# Pg2_B_Terminals_Balancing.net
KiCad netlist of a schematic drawn in Altium Designer
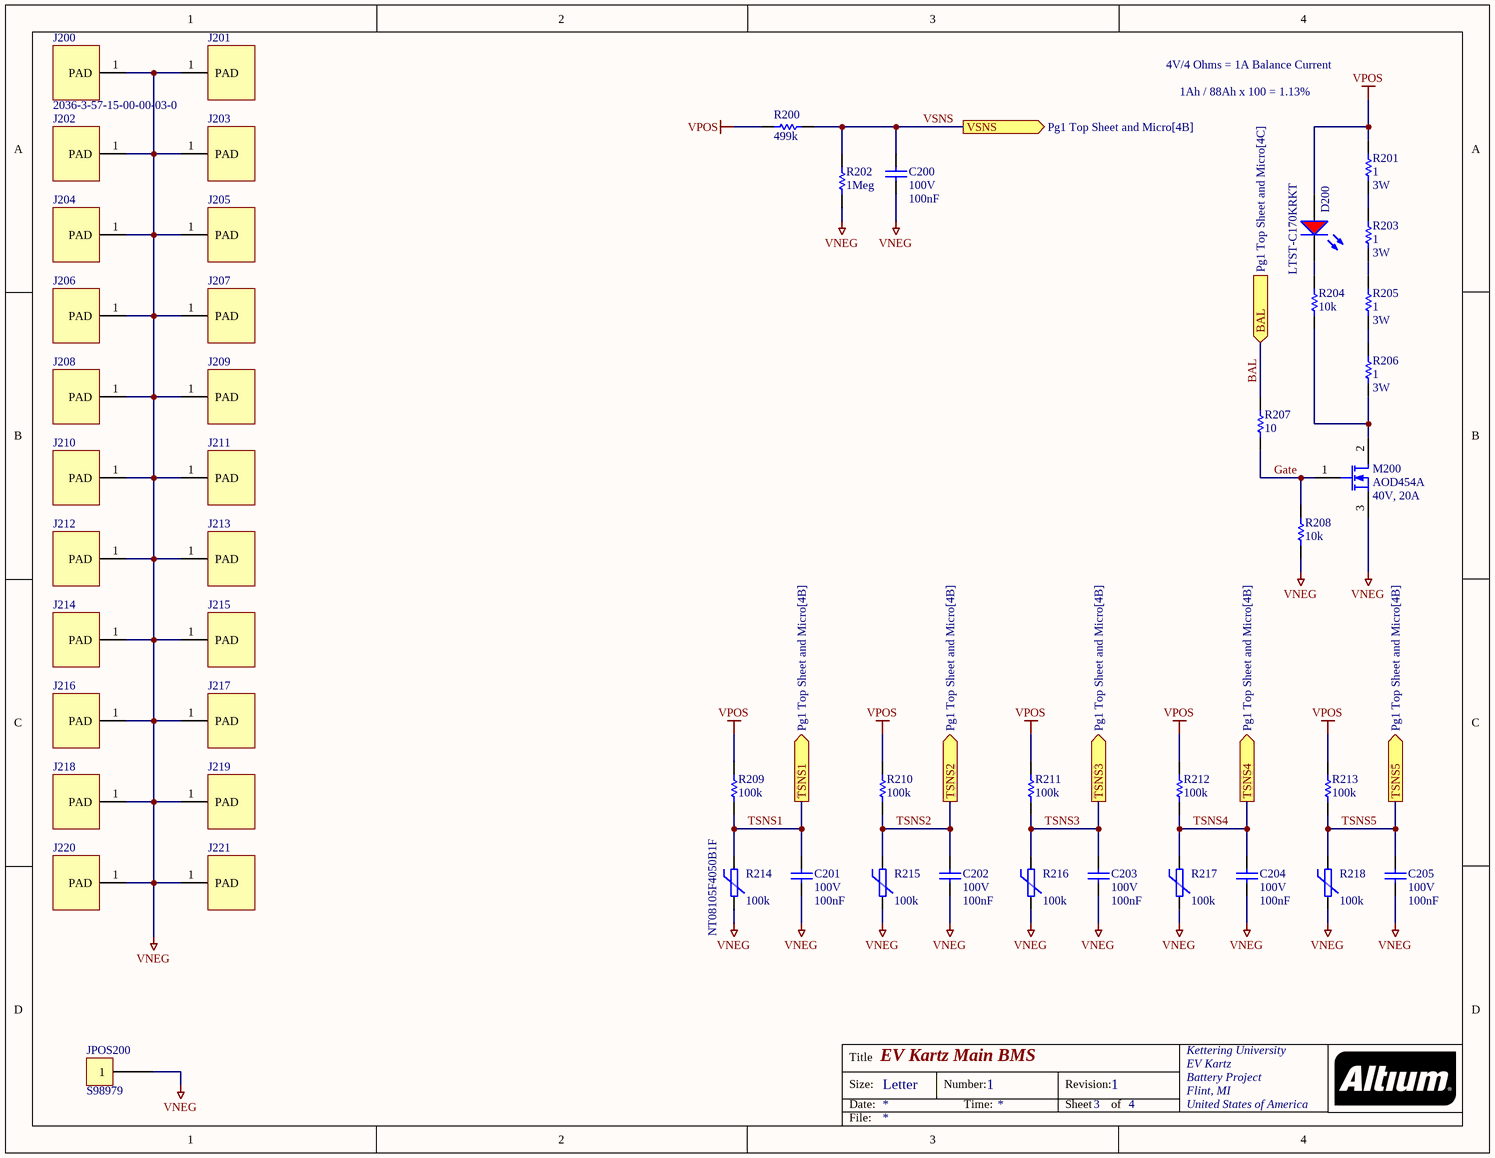
[diagram p0: Pg2 B Terminals & Balancing.SchDoc]

(export (version "E")
  (design (tool "Eeschema 10.0.6"))
  (components
    (comp (ref "C200")
      (value "100nF")
      (footprint "CAPC2012N")
      (description "Capacitor, Ceramic, 100nF, 100V, 0805, 10%, 125C")
      (fields (field (name "RATED") "100V") (field (name "Comment") "C0805C104K1RACAUTO"))
      (libsource (lib "SchLib - EE391 Master") (part "C0805C104K1RACAUTO"))
    )
    (comp (ref "C201")
      (value "100nF")
      (footprint "CAPC2012N")
      (description "Capacitor, Ceramic, 100nF, 100V, 0805, 10%, 125C")
      (fields (field (name "RATED") "100V") (field (name "Comment") "C0805C104K1RACAUTO"))
      (libsource (lib "SchLib - EE391 Master") (part "C0805C104K1RACAUTO"))
    )
    (comp (ref "C202")
      (value "100nF")
      (footprint "CAPC2012N")
      (description "Capacitor, Ceramic, 100nF, 100V, 0805, 10%, 125C")
      (fields (field (name "RATED") "100V") (field (name "Comment") "C0805C104K1RACAUTO"))
      (libsource (lib "SchLib - EE391 Master") (part "C0805C104K1RACAUTO"))
    )
    (comp (ref "C203")
      (value "100nF")
      (footprint "CAPC2012N")
      (description "Capacitor, Ceramic, 100nF, 100V, 0805, 10%, 125C")
      (fields (field (name "RATED") "100V") (field (name "Comment") "C0805C104K1RACAUTO"))
      (libsource (lib "SchLib - EE391 Master") (part "C0805C104K1RACAUTO"))
    )
    (comp (ref "C204")
      (value "100nF")
      (footprint "CAPC2012N")
      (description "Capacitor, Ceramic, 100nF, 100V, 0805, 10%, 125C")
      (fields (field (name "RATED") "100V") (field (name "Comment") "C0805C104K1RACAUTO"))
      (libsource (lib "SchLib - EE391 Master") (part "C0805C104K1RACAUTO"))
    )
    (comp (ref "C205")
      (value "100nF")
      (footprint "CAPC2012N")
      (description "Capacitor, Ceramic, 100nF, 100V, 0805, 10%, 125C")
      (fields (field (name "RATED") "100V") (field (name "Comment") "C0805C104K1RACAUTO"))
      (libsource (lib "SchLib - EE391 Master") (part "C0805C104K1RACAUTO"))
    )
    (comp (ref "D200")
      (value "LTST-C170KRKT")
      (footprint "DIO2012N-R")
      (description "LED, SMT 0805, Red, 2.0V, 20mA")
      (libsource (lib "SchLib - EE391 Master") (part "LTST-C170KRKT"))
    )
    (comp (ref "J200")
      (value "2036-3-57-15-00-00-03-0")
      (footprint "6mm Pad")
      (description "Hardware, Sprint Contact Surface")
      (libsource (lib "") (part "2036-3-57-15-00-00-03-0_1"))
    )
    (comp (ref "J201")
      (value "2036-3-57-15-00-00-03-0")
      (footprint "6mm Pad")
      (description "Hardware, Sprint Contact Surface")
      (libsource (lib "SchLib - EE391 Master") (part "2036-3-57-15-00-00-03-0"))
    )
    (comp (ref "J202")
      (value "2036-3-57-15-00-00-03-0")
      (footprint "6mm Pad")
      (description "Hardware, Sprint Contact Surface")
      (libsource (lib "") (part "2036-3-57-15-00-00-03-0_1"))
    )
    (comp (ref "J203")
      (value "2036-3-57-15-00-00-03-0")
      (footprint "6mm Pad")
      (description "Hardware, Sprint Contact Surface")
      (libsource (lib "SchLib - EE391 Master") (part "2036-3-57-15-00-00-03-0"))
    )
    (comp (ref "J204")
      (value "2036-3-57-15-00-00-03-0")
      (footprint "6mm Pad")
      (description "Hardware, Sprint Contact Surface")
      (libsource (lib "") (part "2036-3-57-15-00-00-03-0_1"))
    )
    (comp (ref "J205")
      (value "2036-3-57-15-00-00-03-0")
      (footprint "6mm Pad")
      (description "Hardware, Sprint Contact Surface")
      (libsource (lib "SchLib - EE391 Master") (part "2036-3-57-15-00-00-03-0"))
    )
    (comp (ref "J206")
      (value "2036-3-57-15-00-00-03-0")
      (footprint "6mm Pad")
      (description "Hardware, Sprint Contact Surface")
      (libsource (lib "") (part "2036-3-57-15-00-00-03-0_1"))
    )
    (comp (ref "J207")
      (value "2036-3-57-15-00-00-03-0")
      (footprint "6mm Pad")
      (description "Hardware, Sprint Contact Surface")
      (libsource (lib "SchLib - EE391 Master") (part "2036-3-57-15-00-00-03-0"))
    )
    (comp (ref "J208")
      (value "2036-3-57-15-00-00-03-0")
      (footprint "6mm Pad")
      (description "Hardware, Sprint Contact Surface")
      (libsource (lib "") (part "2036-3-57-15-00-00-03-0_1"))
    )
    (comp (ref "J209")
      (value "2036-3-57-15-00-00-03-0")
      (footprint "6mm Pad")
      (description "Hardware, Sprint Contact Surface")
      (libsource (lib "SchLib - EE391 Master") (part "2036-3-57-15-00-00-03-0"))
    )
    (comp (ref "J210")
      (value "2036-3-57-15-00-00-03-0")
      (footprint "6mm Pad")
      (description "Hardware, Sprint Contact Surface")
      (libsource (lib "") (part "2036-3-57-15-00-00-03-0_1"))
    )
    (comp (ref "J211")
      (value "2036-3-57-15-00-00-03-0")
      (footprint "6mm Pad")
      (description "Hardware, Sprint Contact Surface")
      (libsource (lib "SchLib - EE391 Master") (part "2036-3-57-15-00-00-03-0"))
    )
    (comp (ref "J212")
      (value "2036-3-57-15-00-00-03-0")
      (footprint "6mm Pad")
      (description "Hardware, Sprint Contact Surface")
      (libsource (lib "") (part "2036-3-57-15-00-00-03-0_1"))
    )
    (comp (ref "J213")
      (value "2036-3-57-15-00-00-03-0")
      (footprint "6mm Pad")
      (description "Hardware, Sprint Contact Surface")
      (libsource (lib "SchLib - EE391 Master") (part "2036-3-57-15-00-00-03-0"))
    )
    (comp (ref "J214")
      (value "2036-3-57-15-00-00-03-0")
      (footprint "6mm Pad")
      (description "Hardware, Sprint Contact Surface")
      (libsource (lib "") (part "2036-3-57-15-00-00-03-0_1"))
    )
    (comp (ref "J215")
      (value "2036-3-57-15-00-00-03-0")
      (footprint "6mm Pad")
      (description "Hardware, Sprint Contact Surface")
      (libsource (lib "SchLib - EE391 Master") (part "2036-3-57-15-00-00-03-0"))
    )
    (comp (ref "J216")
      (value "2036-3-57-15-00-00-03-0")
      (footprint "6mm Pad")
      (description "Hardware, Sprint Contact Surface")
      (libsource (lib "") (part "2036-3-57-15-00-00-03-0_1"))
    )
    (comp (ref "J217")
      (value "2036-3-57-15-00-00-03-0")
      (footprint "6mm Pad")
      (description "Hardware, Sprint Contact Surface")
      (libsource (lib "SchLib - EE391 Master") (part "2036-3-57-15-00-00-03-0"))
    )
    (comp (ref "J218")
      (value "2036-3-57-15-00-00-03-0")
      (footprint "6mm Pad")
      (description "Hardware, Sprint Contact Surface")
      (libsource (lib "") (part "2036-3-57-15-00-00-03-0_1"))
    )
    (comp (ref "J219")
      (value "2036-3-57-15-00-00-03-0")
      (footprint "6mm Pad")
      (description "Hardware, Sprint Contact Surface")
      (libsource (lib "SchLib - EE391 Master") (part "2036-3-57-15-00-00-03-0"))
    )
    (comp (ref "J220")
      (value "2036-3-57-15-00-00-03-0")
      (footprint "6mm Pad")
      (description "Hardware, Sprint Contact Surface")
      (libsource (lib "") (part "2036-3-57-15-00-00-03-0_1"))
    )
    (comp (ref "J221")
      (value "2036-3-57-15-00-00-03-0")
      (footprint "6mm Pad")
      (description "Hardware, Sprint Contact Surface")
      (libsource (lib "SchLib - EE391 Master") (part "2036-3-57-15-00-00-03-0"))
    )
    (comp (ref "JPOS200")
      (value "S98979")
      (footprint "S98979")
      (description "Screw Terminal M8, 360A")
      (libsource (lib "Connectors") (part "S98979"))
    )
    (comp (ref "M200")
      (value "AOD454A")
      (footprint "TO252-3N")
      (description "MOSFET, N-Ch, 40V, 20A, 430mOhm, TO252")
      (fields (field (name "RATED") "40V, 20A"))
      (libsource (lib "SchLib - EE391 Master") (part "AOD454A"))
    )
    (comp (ref "R200")
      (value "499k")
      (footprint "RESC2012N")
      (description "Resistor, Fixed, 499 kOhm, 0805, 1%, 1/8W")
      (fields (field (name "Comment") "ERJ-6ENF4993V"))
      (libsource (lib "SchLib - EE391 Master") (part "ERJ-6ENF4993V"))
    )
    (comp (ref "R201")
      (value "1")
      (footprint "RESC6432N")
      (description "Resistor, Power, 1 Ohm, 6432, 5%, 3W")
      (fields (field (name "RATED") "3W") (field (name "Comment") "35221R0JT"))
      (libsource (lib "SchLib - EE391 Master") (part "35221R0JT"))
    )
    (comp (ref "R202")
      (value "1Meg")
      (footprint "RESC2012N")
      (description "Resistor, Fixed, 1 MOhm, 0805, 1%, 1/8W")
      (fields (field (name "Comment") "ERJ-6ENF1004V"))
      (libsource (lib "SchLib - EE391 Master") (part "ERJ-6ENF1004V"))
    )
    (comp (ref "R203")
      (value "1")
      (footprint "RESC6432N")
      (description "Resistor, Power, 1 Ohm, 6432, 5%, 3W")
      (fields (field (name "RATED") "3W") (field (name "Comment") "35221R0JT"))
      (libsource (lib "SchLib - EE391 Master") (part "35221R0JT"))
    )
    (comp (ref "R204")
      (value "10k")
      (footprint "RESC2012N")
      (description "Resistor, Fixed, 10 kOhm, 0805, 1%, 1/8W")
      (fields (field (name "Comment") "ERJ-6ENF1002V"))
      (libsource (lib "SchLib - EE391 Master") (part "ERJ-6ENF1002V"))
    )
    (comp (ref "R205")
      (value "1")
      (footprint "RESC6432N")
      (description "Resistor, Power, 1 Ohm, 6432, 5%, 3W")
      (fields (field (name "RATED") "3W") (field (name "Comment") "35221R0JT"))
      (libsource (lib "SchLib - EE391 Master") (part "35221R0JT"))
    )
    (comp (ref "R206")
      (value "1")
      (footprint "RESC6432N")
      (description "Resistor, Power, 1 Ohm, 6432, 5%, 3W")
      (fields (field (name "RATED") "3W") (field (name "Comment") "35221R0JT"))
      (libsource (lib "SchLib - EE391 Master") (part "35221R0JT"))
    )
    (comp (ref "R207")
      (value "10")
      (footprint "RESC2012N")
      (description "Resistor, Fixed, 10 Ohm, 0805, 1%, 1/8W")
      (fields (field (name "Comment") "ERJ-6ENF10R0V"))
      (libsource (lib "SchLib - EE391 Master") (part "ERJ-6ENF10R0V"))
    )
    (comp (ref "R208")
      (value "10k")
      (footprint "RESC2012N")
      (description "Resistor, Fixed, 10 kOhm, 0805, 1%, 1/8W")
      (fields (field (name "Comment") "ERJ-6ENF1002V"))
      (libsource (lib "SchLib - EE391 Master") (part "ERJ-6ENF1002V"))
    )
    (comp (ref "R209")
      (value "100k")
      (footprint "RESC2012N")
      (description "Resistor, Fixed, 100 kOhm, 0805, 1%, 1/8W")
      (fields (field (name "Comment") "ERJ-6ENF1003V"))
      (libsource (lib "SchLib - EE391 Master") (part "ERJ-6ENF1003V"))
    )
    (comp (ref "R210")
      (value "100k")
      (footprint "RESC2012N")
      (description "Resistor, Fixed, 100 kOhm, 0805, 1%, 1/8W")
      (fields (field (name "Comment") "ERJ-6ENF1003V"))
      (libsource (lib "SchLib - EE391 Master") (part "ERJ-6ENF1003V"))
    )
    (comp (ref "R211")
      (value "100k")
      (footprint "RESC2012N")
      (description "Resistor, Fixed, 100 kOhm, 0805, 1%, 1/8W")
      (fields (field (name "Comment") "ERJ-6ENF1003V"))
      (libsource (lib "SchLib - EE391 Master") (part "ERJ-6ENF1003V"))
    )
    (comp (ref "R212")
      (value "100k")
      (footprint "RESC2012N")
      (description "Resistor, Fixed, 100 kOhm, 0805, 1%, 1/8W")
      (fields (field (name "Comment") "ERJ-6ENF1003V"))
      (libsource (lib "SchLib - EE391 Master") (part "ERJ-6ENF1003V"))
    )
    (comp (ref "R213")
      (value "100k")
      (footprint "RESC2012N")
      (description "Resistor, Fixed, 100 kOhm, 0805, 1%, 1/8W")
      (fields (field (name "Comment") "ERJ-6ENF1003V"))
      (libsource (lib "SchLib - EE391 Master") (part "ERJ-6ENF1003V"))
    )
    (comp (ref "R214")
      (value "NT08105F4050B1F")
      (footprint "RESC2012N")
      (description "Resistor, NTC Thermistor, 100kOhm, 0805, 1%, 125C")
      (fields (field (name "ALTIUM_VALUE") "100k"))
      (libsource (lib "SchLib - EE391 Master") (part "NTCS0805E3103FMT"))
    )
    (comp (ref "R215")
      (value "100k")
      (footprint "RESC2012N")
      (description "Resistor, NTC Thermistor, 100kOhm, 0805, 1%, 125C")
      (fields (field (name "Comment") "NT08105F4050B1F"))
      (libsource (lib "SchLib - EE391 Master") (part "NTCS0805E3103FMT"))
    )
    (comp (ref "R216")
      (value "100k")
      (footprint "RESC2012N")
      (description "Resistor, NTC Thermistor, 100kOhm, 0805, 1%, 125C")
      (fields (field (name "Comment") "NT08105F4050B1F"))
      (libsource (lib "SchLib - EE391 Master") (part "NTCS0805E3103FMT"))
    )
    (comp (ref "R217")
      (value "100k")
      (footprint "RESC2012N")
      (description "Resistor, NTC Thermistor, 100kOhm, 0805, 1%, 125C")
      (fields (field (name "Comment") "NT08105F4050B1F"))
      (libsource (lib "SchLib - EE391 Master") (part "NTCS0805E3103FMT"))
    )
    (comp (ref "R218")
      (value "100k")
      (footprint "RESC2012N")
      (description "Resistor, NTC Thermistor, 100kOhm, 0805, 1%, 125C")
      (fields (field (name "Comment") "NT08105F4050B1F"))
      (libsource (lib "SchLib - EE391 Master") (part "NTCS0805E3103FMT"))
    )
  )
  (nets
    (net (code "1") (name "/BAL") (class "Default")
      (node (ref "R207") (pin "2") (pinfunction "2_2") (pintype "passive"))
    )
    (net (code "2") (name "/Gate") (class "Default")
      (node (ref "M200") (pin "1") (pinfunction "G_1") (pintype "passive"))
      (node (ref "R207") (pin "1") (pinfunction "1_1") (pintype "passive"))
      (node (ref "R208") (pin "2") (pinfunction "2_2") (pintype "passive"))
    )
    (net (code "3") (name "/TSNS1") (class "Default")
      (node (ref "C201") (pin "1") (pinfunction "1_1") (pintype "passive"))
      (node (ref "R209") (pin "1") (pinfunction "1_1") (pintype "passive"))
      (node (ref "R214") (pin "1") (pinfunction "1_1") (pintype "passive"))
    )
    (net (code "4") (name "/TSNS2") (class "Default")
      (node (ref "C202") (pin "1") (pinfunction "1_1") (pintype "passive"))
      (node (ref "R210") (pin "1") (pinfunction "1_1") (pintype "passive"))
      (node (ref "R215") (pin "1") (pinfunction "1_1") (pintype "passive"))
    )
    (net (code "5") (name "/TSNS3") (class "Default")
      (node (ref "C203") (pin "1") (pinfunction "1_1") (pintype "passive"))
      (node (ref "R211") (pin "1") (pinfunction "1_1") (pintype "passive"))
      (node (ref "R216") (pin "1") (pinfunction "1_1") (pintype "passive"))
    )
    (net (code "6") (name "/TSNS4") (class "Default")
      (node (ref "C204") (pin "1") (pinfunction "1_1") (pintype "passive"))
      (node (ref "R212") (pin "1") (pinfunction "1_1") (pintype "passive"))
      (node (ref "R217") (pin "1") (pinfunction "1_1") (pintype "passive"))
    )
    (net (code "7") (name "/TSNS5") (class "Default")
      (node (ref "C205") (pin "1") (pinfunction "1_1") (pintype "passive"))
      (node (ref "R213") (pin "1") (pinfunction "1_1") (pintype "passive"))
      (node (ref "R218") (pin "1") (pinfunction "1_1") (pintype "passive"))
    )
    (net (code "8") (name "/VSNS") (class "Default")
      (node (ref "C200") (pin "1") (pinfunction "1_1") (pintype "passive"))
      (node (ref "R200") (pin "1") (pinfunction "1_1") (pintype "passive"))
      (node (ref "R202") (pin "2") (pinfunction "2_2") (pintype "passive"))
    )
    (net (code "9") (name "Net-(D200-K)") (class "Default")
      (node (ref "D200") (pin "2") (pinfunction "K_2") (pintype "passive"))
      (node (ref "R204") (pin "2") (pinfunction "2_2") (pintype "passive"))
    )
    (net (code "10") (name "Net-(M200-D)") (class "Default")
      (node (ref "M200") (pin "2") (pinfunction "D_2") (pintype "passive"))
      (node (ref "R204") (pin "1") (pinfunction "1_1") (pintype "passive"))
      (node (ref "R206") (pin "1") (pinfunction "1_1") (pintype "passive"))
    )
    (net (code "11") (name "Net-(R201-Pad1)") (class "Default")
      (node (ref "R201") (pin "1") (pinfunction "1_1") (pintype "passive"))
      (node (ref "R203") (pin "2") (pinfunction "2_2") (pintype "passive"))
    )
    (net (code "12") (name "Net-(R203-Pad1)") (class "Default")
      (node (ref "R203") (pin "1") (pinfunction "1_1") (pintype "passive"))
      (node (ref "R205") (pin "2") (pinfunction "2_2") (pintype "passive"))
    )
    (net (code "13") (name "Net-(R205-Pad1)") (class "Default")
      (node (ref "R205") (pin "1") (pinfunction "1_1") (pintype "passive"))
      (node (ref "R206") (pin "2") (pinfunction "2_2") (pintype "passive"))
    )
    (net (code "14") (name "VNEG") (class "Default")
      (node (ref "C200") (pin "2") (pinfunction "2_2") (pintype "passive"))
      (node (ref "C201") (pin "2") (pinfunction "2_2") (pintype "passive"))
      (node (ref "C202") (pin "2") (pinfunction "2_2") (pintype "passive"))
      (node (ref "C203") (pin "2") (pinfunction "2_2") (pintype "passive"))
      (node (ref "C204") (pin "2") (pinfunction "2_2") (pintype "passive"))
      (node (ref "C205") (pin "2") (pinfunction "2_2") (pintype "passive"))
      (node (ref "J200") (pin "1") (pinfunction "PAD_1") (pintype "passive"))
      (node (ref "J201") (pin "1") (pinfunction "PAD_1") (pintype "passive"))
      (node (ref "J202") (pin "1") (pinfunction "PAD_1") (pintype "passive"))
      (node (ref "J203") (pin "1") (pinfunction "PAD_1") (pintype "passive"))
      (node (ref "J204") (pin "1") (pinfunction "PAD_1") (pintype "passive"))
      (node (ref "J205") (pin "1") (pinfunction "PAD_1") (pintype "passive"))
      (node (ref "J206") (pin "1") (pinfunction "PAD_1") (pintype "passive"))
      (node (ref "J207") (pin "1") (pinfunction "PAD_1") (pintype "passive"))
      (node (ref "J208") (pin "1") (pinfunction "PAD_1") (pintype "passive"))
      (node (ref "J209") (pin "1") (pinfunction "PAD_1") (pintype "passive"))
      (node (ref "J210") (pin "1") (pinfunction "PAD_1") (pintype "passive"))
      (node (ref "J211") (pin "1") (pinfunction "PAD_1") (pintype "passive"))
      (node (ref "J212") (pin "1") (pinfunction "PAD_1") (pintype "passive"))
      (node (ref "J213") (pin "1") (pinfunction "PAD_1") (pintype "passive"))
      (node (ref "J214") (pin "1") (pinfunction "PAD_1") (pintype "passive"))
      (node (ref "J215") (pin "1") (pinfunction "PAD_1") (pintype "passive"))
      (node (ref "J216") (pin "1") (pinfunction "PAD_1") (pintype "passive"))
      (node (ref "J217") (pin "1") (pinfunction "PAD_1") (pintype "passive"))
      (node (ref "J218") (pin "1") (pinfunction "PAD_1") (pintype "passive"))
      (node (ref "J219") (pin "1") (pinfunction "PAD_1") (pintype "passive"))
      (node (ref "J220") (pin "1") (pinfunction "PAD_1") (pintype "passive"))
      (node (ref "J221") (pin "1") (pinfunction "PAD_1") (pintype "passive"))
      (node (ref "JPOS200") (pin "1") (pinfunction "1_1") (pintype "passive"))
      (node (ref "M200") (pin "3") (pinfunction "S_3") (pintype "passive"))
      (node (ref "R202") (pin "1") (pinfunction "1_1") (pintype "passive"))
      (node (ref "R208") (pin "1") (pinfunction "1_1") (pintype "passive"))
      (node (ref "R214") (pin "2") (pinfunction "2_2") (pintype "passive"))
      (node (ref "R215") (pin "2") (pinfunction "2_2") (pintype "passive"))
      (node (ref "R216") (pin "2") (pinfunction "2_2") (pintype "passive"))
      (node (ref "R217") (pin "2") (pinfunction "2_2") (pintype "passive"))
      (node (ref "R218") (pin "2") (pinfunction "2_2") (pintype "passive"))
    )
    (net (code "15") (name "VPOS") (class "Default")
      (node (ref "D200") (pin "1") (pinfunction "A_1") (pintype "passive"))
      (node (ref "R200") (pin "2") (pinfunction "2_2") (pintype "passive"))
      (node (ref "R201") (pin "2") (pinfunction "2_2") (pintype "passive"))
      (node (ref "R209") (pin "2") (pinfunction "2_2") (pintype "passive"))
      (node (ref "R210") (pin "2") (pinfunction "2_2") (pintype "passive"))
      (node (ref "R211") (pin "2") (pinfunction "2_2") (pintype "passive"))
      (node (ref "R212") (pin "2") (pinfunction "2_2") (pintype "passive"))
      (node (ref "R213") (pin "2") (pinfunction "2_2") (pintype "passive"))
    )
  )
)
